# Slave-Mega.net
KiCad netlist of a schematic drawn in EAGLE
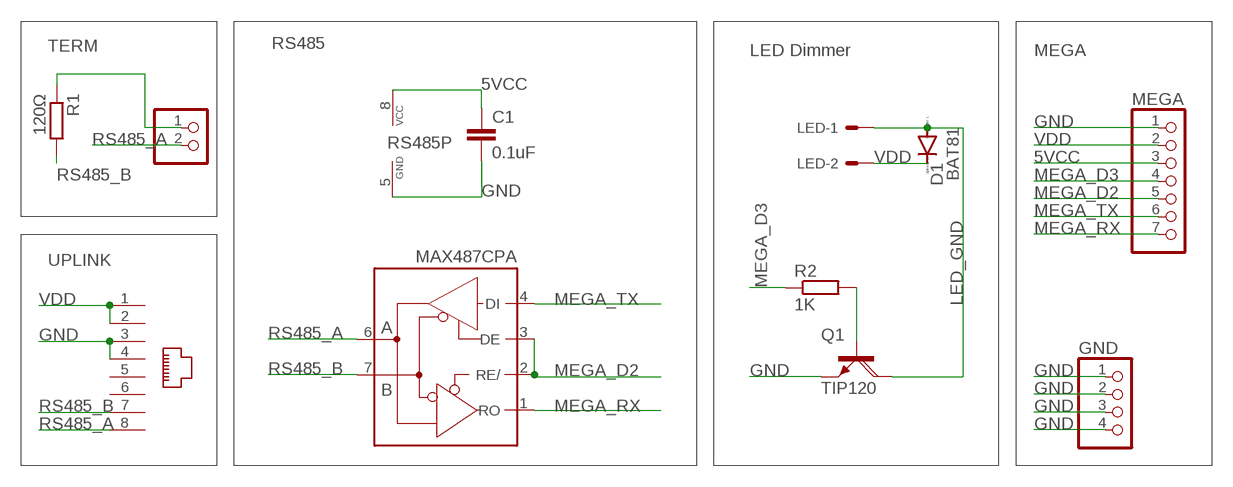
[diagram p0: schematic, sheet 1]

(export (version "E")
  (design (tool "Eeschema 10.0.6"))
  (components
    (comp (ref "C1")
      (value "0.1uF")
      (footprint "eagle-import:C025-025X050")
      (libsource (lib "eagle-import") (part "C-EU025-025X050"))
    )
    (comp (ref "D1")
      (value "BAT81")
      (footprint "eagle-import:DO34-7")
      (libsource (lib "eagle-import") (part "BAT81"))
    )
    (comp (ref "GND")
      (value "PINHD-1X4")
      (footprint "eagle-import:1X04")
      (libsource (lib "eagle-import") (part "PINHD-1X4"))
    )
    (comp (ref "LED")
      (value "KK-156-2")
      (footprint "eagle-import:KK-156-2")
      (fields (field (name "MF") "MOLEX"))
      (libsource (lib "eagle-import") (part "KK-156-2"))
    )
    (comp (ref "MEGA")
      (value "PINHD-1X7")
      (footprint "eagle-import:1X07")
      (libsource (lib "eagle-import") (part "PINHD-1X7"))
    )
    (comp (ref "Q1")
      (value "TIP120")
      (footprint "eagle-import:TO220AH")
      (libsource (lib "eagle-import") (part "TIP120"))
    )
    (comp (ref "R1")
      (value "120Ω")
      (footprint "eagle-import:0204_7")
      (libsource (lib "eagle-import") (part "R-EU_0204/7"))
    )
    (comp (ref "R2")
      (value "1K")
      (footprint "eagle-import:0204_7")
      (libsource (lib "eagle-import") (part "R-EU_0204/7"))
    )
    (comp (ref "RS485")
      (value "MAX487CPA")
      (footprint "eagle-import:DIL08")
      (libsource (lib "eagle-import") (part "MAX487CPA"))
    )
    (comp (ref "TERM")
      (value "PINHD-1X2")
      (footprint "eagle-import:1X02")
      (libsource (lib "eagle-import") (part "PINHD-1X2"))
    )
    (comp (ref "UPLINK")
      (value "RJ45-8P8C")
      (footprint "eagle-import:RJ45-8P8C")
      (libsource (lib "eagle-import") (part "RJ45-8P8C"))
    )
  )
  (nets
    (net (code "1") (name "/5VCC") (class "Default")
      (node (ref "C1") (pin "1") (pinfunction "1_1") (pintype "passive"))
      (node (ref "MEGA") (pin "3") (pinfunction "3_3") (pintype "passive"))
      (node (ref "RS485") (pin "8") (pinfunction "VCC_8") (pintype "power_in"))
    )
    (net (code "2") (name "/GND") (class "Default")
      (node (ref "C1") (pin "2") (pinfunction "2_2") (pintype "passive"))
      (node (ref "GND") (pin "1") (pinfunction "1_1") (pintype "passive"))
      (node (ref "GND") (pin "2") (pinfunction "2_2") (pintype "passive"))
      (node (ref "GND") (pin "3") (pinfunction "3_3") (pintype "passive"))
      (node (ref "GND") (pin "4") (pinfunction "4_4") (pintype "passive"))
      (node (ref "MEGA") (pin "1") (pinfunction "1_1") (pintype "passive"))
      (node (ref "Q1") (pin "E") (pinfunction "E_E") (pintype "passive"))
      (node (ref "RS485") (pin "5") (pinfunction "GND_5") (pintype "power_in"))
      (node (ref "UPLINK") (pin "3") (pinfunction "3_3") (pintype "bidirectional"))
      (node (ref "UPLINK") (pin "4") (pinfunction "4_4") (pintype "bidirectional"))
    )
    (net (code "3") (name "/LED_GND") (class "Default")
      (node (ref "D1") (pin "A") (pinfunction "A_A") (pintype "passive"))
      (node (ref "LED") (pin "1") (pinfunction "S_1") (pintype "passive"))
      (node (ref "Q1") (pin "C") (pinfunction "C_C") (pintype "passive"))
    )
    (net (code "4") (name "/MEGA_D2") (class "Default")
      (node (ref "MEGA") (pin "5") (pinfunction "5_5") (pintype "passive"))
      (node (ref "RS485") (pin "2") (pinfunction "RE/_2") (pintype "input"))
      (node (ref "RS485") (pin "3") (pinfunction "DE_3") (pintype "input"))
    )
    (net (code "5") (name "/MEGA_D3") (class "Default")
      (node (ref "MEGA") (pin "4") (pinfunction "4_4") (pintype "passive"))
      (node (ref "R2") (pin "1") (pinfunction "1_1") (pintype "passive"))
    )
    (net (code "6") (name "/MEGA_RX") (class "Default")
      (node (ref "MEGA") (pin "7") (pinfunction "7_7") (pintype "passive"))
      (node (ref "RS485") (pin "1") (pinfunction "RO_1") (pintype "output"))
    )
    (net (code "7") (name "/MEGA_TX") (class "Default")
      (node (ref "MEGA") (pin "6") (pinfunction "6_6") (pintype "passive"))
      (node (ref "RS485") (pin "4") (pinfunction "DI_4") (pintype "input"))
    )
    (net (code "8") (name "/RS485_A") (class "Default")
      (node (ref "RS485") (pin "6") (pinfunction "A_6") (pintype "passive"))
      (node (ref "TERM") (pin "2") (pinfunction "2_2") (pintype "passive"))
      (node (ref "UPLINK") (pin "8") (pinfunction "8_8") (pintype "bidirectional"))
    )
    (net (code "9") (name "/RS485_B") (class "Default")
      (node (ref "R1") (pin "2") (pinfunction "2_2") (pintype "passive"))
      (node (ref "RS485") (pin "7") (pinfunction "B_7") (pintype "passive"))
      (node (ref "UPLINK") (pin "7") (pinfunction "7_7") (pintype "bidirectional"))
    )
    (net (code "10") (name "/VDD") (class "Default")
      (node (ref "D1") (pin "C") (pinfunction "C_C") (pintype "passive"))
      (node (ref "LED") (pin "2") (pinfunction "S_2") (pintype "passive"))
      (node (ref "MEGA") (pin "2") (pinfunction "2_2") (pintype "passive"))
      (node (ref "UPLINK") (pin "1") (pinfunction "1_1") (pintype "bidirectional"))
      (node (ref "UPLINK") (pin "2") (pinfunction "2_2") (pintype "bidirectional"))
    )
    (net (code "11") (name "Net-(Q1-PadB)") (class "Default")
      (node (ref "Q1") (pin "B") (pinfunction "B_B") (pintype "passive"))
      (node (ref "R2") (pin "2") (pinfunction "2_2") (pintype "passive"))
    )
    (net (code "12") (name "Net-(R1-Pad1)") (class "Default")
      (node (ref "R1") (pin "1") (pinfunction "1_1") (pintype "passive"))
      (node (ref "TERM") (pin "1") (pinfunction "1_1") (pintype "passive"))
    )
    (net (code "13") (name "unconnected-(UPLINK-Pad5)") (class "Default")
      (node (ref "UPLINK") (pin "5") (pinfunction "5_5") (pintype "bidirectional"))
    )
    (net (code "14") (name "unconnected-(UPLINK-Pad6)") (class "Default")
      (node (ref "UPLINK") (pin "6") (pinfunction "6_6") (pintype "bidirectional"))
    )
  )
)
